# modem-breakout.net
KiCad netlist of a schematic drawn in EAGLE
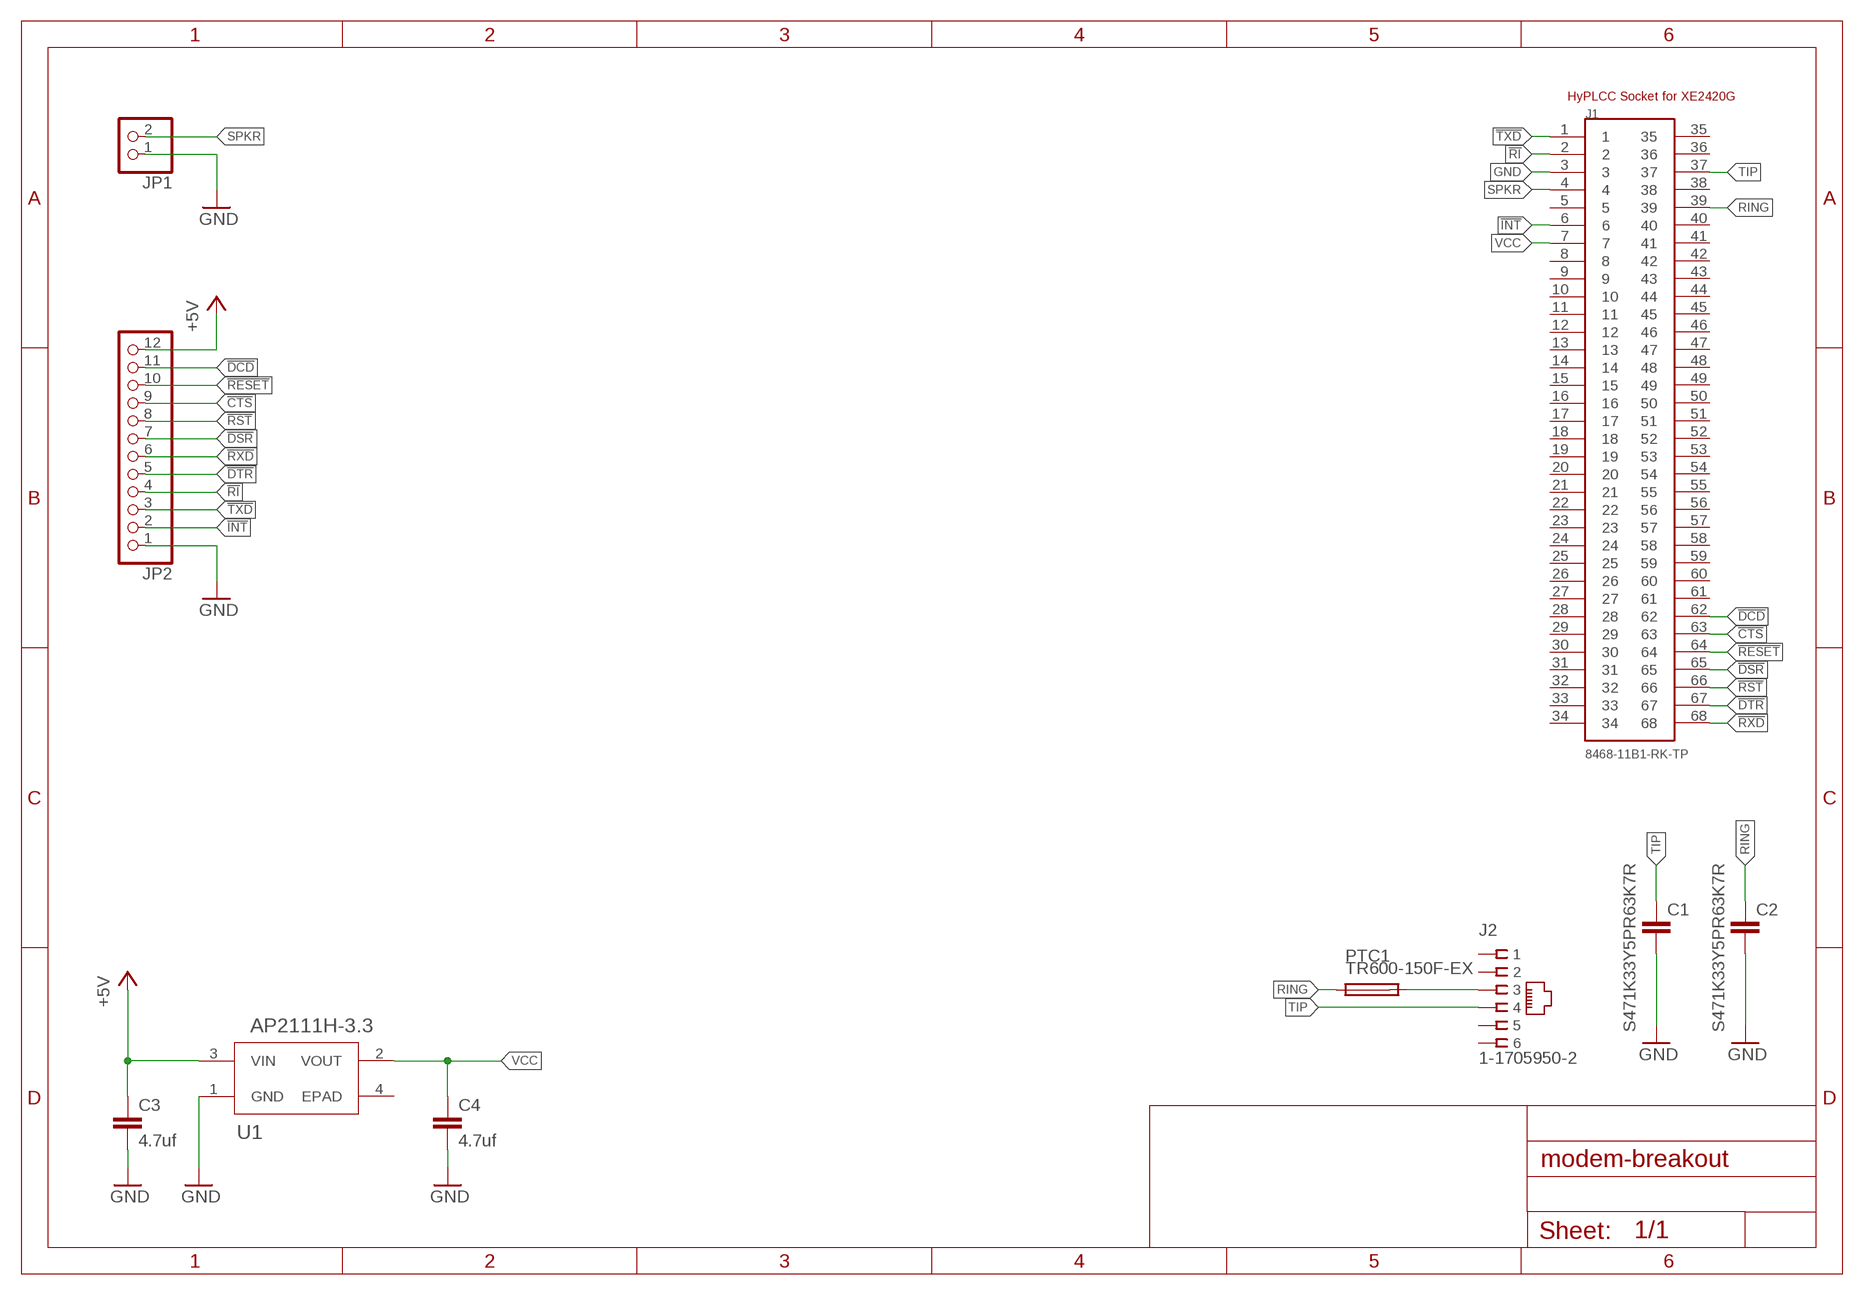
[diagram p0: schematic, sheet 1]

(export (version "E")
  (design (tool "Eeschema 10.0.6"))
  (components
    (comp (ref "C1")
      (value "S471K33Y5PR63K7R")
      (footprint "eagle-import:C075-052X106")
      (libsource (lib "eagle-import") (part "C-EU075-052X106"))
    )
    (comp (ref "C2")
      (value "S471K33Y5PR63K7R")
      (footprint "eagle-import:C075-052X106")
      (libsource (lib "eagle-import") (part "C-EU075-052X106"))
    )
    (comp (ref "C3")
      (value "4.7uf")
      (footprint "eagle-import:C0805")
      (libsource (lib "eagle-import") (part "C-EUC0805"))
    )
    (comp (ref "C4")
      (value "4.7uf")
      (footprint "eagle-import:C0805")
      (libsource (lib "eagle-import") (part "C-EUC0805"))
    )
    (comp (ref "J1")
      (value "8468-11B1-RK-TP")
      (footprint "eagle-import:3M_8468-11B1-RK-TP")
      (fields (field (name "MF") "3M"))
      (libsource (lib "eagle-import") (part "8468-11B1-RK-TP"))
    )
    (comp (ref "J2")
      (value "1-1705950-2")
      (footprint "eagle-import:RJ11-NO_SHIELD")
      (fields (field (name "MF") "TYCO ELECTRONICS") (field (name "MPN") "RJ11-2L-B"))
      (libsource (lib "eagle-import") (part "RJ11-2L-B"))
    )
    (comp (ref "JP1")
      (value "PINHD-1X2")
      (footprint "eagle-import:1X02")
      (libsource (lib "eagle-import") (part "PINHD-1X2"))
    )
    (comp (ref "JP2")
      (value "PINHD-1X12")
      (footprint "eagle-import:1X12")
      (libsource (lib "eagle-import") (part "PINHD-1X12"))
    )
    (comp (ref "PTC1")
      (value "TR600-150F-EX")
      (footprint "eagle-import:13.50X6.00")
      (libsource (lib "eagle-import") (part "TR600-150F-EX"))
    )
    (comp (ref "U1")
      (value "AP2111H-3.3")
      (footprint "eagle-import:SOT-223_DIO-M")
      (fields (field (name "MANUFACTURER_PART_NUMBER") "AP2111H-3.3TRG1"))
      (libsource (lib "eagle-import") (part "AP2111H-3.3TRG1SOT-223_DIO-M"))
    )
  )
  (nets
    (net (code "1") (name "+5V") (class "Default")
      (node (ref "C3") (pin "1") (pinfunction "1_1") (pintype "passive"))
      (node (ref "JP2") (pin "12") (pinfunction "12_12") (pintype "passive"))
      (node (ref "U1") (pin "3") (pinfunction "VIN_3") (pintype "input"))
    )
    (net (code "2") (name "/~{CTS}") (class "Default")
      (node (ref "J1") (pin "63") (pinfunction "63_63") (pintype "passive"))
      (node (ref "JP2") (pin "9") (pinfunction "9_9") (pintype "passive"))
    )
    (net (code "3") (name "/~{DCD}") (class "Default")
      (node (ref "J1") (pin "62") (pinfunction "62_62") (pintype "passive"))
      (node (ref "JP2") (pin "11") (pinfunction "11_11") (pintype "passive"))
    )
    (net (code "4") (name "/~{DSR}") (class "Default")
      (node (ref "J1") (pin "65") (pinfunction "65_65") (pintype "passive"))
      (node (ref "JP2") (pin "7") (pinfunction "7_7") (pintype "passive"))
    )
    (net (code "5") (name "/~{DTR}") (class "Default")
      (node (ref "J1") (pin "67") (pinfunction "67_67") (pintype "passive"))
      (node (ref "JP2") (pin "5") (pinfunction "5_5") (pintype "passive"))
    )
    (net (code "6") (name "/~{INT}") (class "Default")
      (node (ref "J1") (pin "6") (pinfunction "6_6") (pintype "passive"))
      (node (ref "JP2") (pin "2") (pinfunction "2_2") (pintype "passive"))
    )
    (net (code "7") (name "/~{RESET}") (class "Default")
      (node (ref "J1") (pin "64") (pinfunction "64_64") (pintype "passive"))
      (node (ref "JP2") (pin "10") (pinfunction "10_10") (pintype "passive"))
    )
    (net (code "8") (name "/~{RI}") (class "Default")
      (node (ref "J1") (pin "2") (pinfunction "2_2") (pintype "passive"))
      (node (ref "JP2") (pin "4") (pinfunction "4_4") (pintype "passive"))
    )
    (net (code "9") (name "/~{RST}") (class "Default")
      (node (ref "J1") (pin "66") (pinfunction "66_66") (pintype "passive"))
      (node (ref "JP2") (pin "8") (pinfunction "8_8") (pintype "passive"))
    )
    (net (code "10") (name "/~{RXD}") (class "Default")
      (node (ref "J1") (pin "68") (pinfunction "68_68") (pintype "passive"))
      (node (ref "JP2") (pin "6") (pinfunction "6_6") (pintype "passive"))
    )
    (net (code "11") (name "/~{TXD}") (class "Default")
      (node (ref "J1") (pin "1") (pinfunction "1_1") (pintype "passive"))
      (node (ref "JP2") (pin "3") (pinfunction "3_3") (pintype "passive"))
    )
    (net (code "12") (name "GND") (class "Default")
      (node (ref "C1") (pin "2") (pinfunction "2_2") (pintype "passive"))
      (node (ref "C2") (pin "2") (pinfunction "2_2") (pintype "passive"))
      (node (ref "C3") (pin "2") (pinfunction "2_2") (pintype "passive"))
      (node (ref "C4") (pin "2") (pinfunction "2_2") (pintype "passive"))
      (node (ref "J1") (pin "3") (pinfunction "3_3") (pintype "passive"))
      (node (ref "JP1") (pin "1") (pinfunction "1_1") (pintype "passive"))
      (node (ref "JP2") (pin "1") (pinfunction "1_1") (pintype "passive"))
      (node (ref "U1") (pin "1") (pinfunction "GND_1") (pintype "power_in"))
    )
    (net (code "13") (name "Net-(PTC1-2)") (class "Default")
      (node (ref "J2") (pin "3") (pinfunction "3_3") (pintype "passive"))
      (node (ref "PTC1") (pin "P$2") (pinfunction "2_P$2") (pintype "passive"))
    )
    (net (code "14") (name "RING") (class "Default")
      (node (ref "C2") (pin "1") (pinfunction "1_1") (pintype "passive"))
      (node (ref "J1") (pin "39") (pinfunction "39_39") (pintype "passive"))
      (node (ref "PTC1") (pin "P$1") (pinfunction "1_P$1") (pintype "passive"))
    )
    (net (code "15") (name "SPKR") (class "Default")
      (node (ref "J1") (pin "4") (pinfunction "4_4") (pintype "passive"))
      (node (ref "JP1") (pin "2") (pinfunction "2_2") (pintype "passive"))
    )
    (net (code "16") (name "TIP") (class "Default")
      (node (ref "C1") (pin "1") (pinfunction "1_1") (pintype "passive"))
      (node (ref "J1") (pin "37") (pinfunction "37_37") (pintype "passive"))
      (node (ref "J2") (pin "4") (pinfunction "4_4") (pintype "passive"))
    )
    (net (code "17") (name "VCC") (class "Default")
      (node (ref "C4") (pin "1") (pinfunction "1_1") (pintype "passive"))
      (node (ref "J1") (pin "7") (pinfunction "7_7") (pintype "passive"))
      (node (ref "U1") (pin "2") (pinfunction "VOUT_2") (pintype "output"))
    )
    (net (code "18") (name "unconnected-(J1-Pad5)") (class "Default")
      (node (ref "J1") (pin "5") (pinfunction "5_5") (pintype "passive"))
    )
    (net (code "19") (name "unconnected-(J1-Pad8)") (class "Default")
      (node (ref "J1") (pin "8") (pinfunction "8_8") (pintype "passive"))
    )
    (net (code "20") (name "unconnected-(J1-Pad9)") (class "Default")
      (node (ref "J1") (pin "9") (pinfunction "9_9") (pintype "passive"))
    )
    (net (code "21") (name "unconnected-(J1-Pad10)") (class "Default")
      (node (ref "J1") (pin "10") (pinfunction "10_10") (pintype "passive"))
    )
    (net (code "22") (name "unconnected-(J1-Pad11)") (class "Default")
      (node (ref "J1") (pin "11") (pinfunction "11_11") (pintype "passive"))
    )
    (net (code "23") (name "unconnected-(J1-Pad12)") (class "Default")
      (node (ref "J1") (pin "12") (pinfunction "12_12") (pintype "passive"))
    )
    (net (code "24") (name "unconnected-(J1-Pad13)") (class "Default")
      (node (ref "J1") (pin "13") (pinfunction "13_13") (pintype "passive"))
    )
    (net (code "25") (name "unconnected-(J1-Pad14)") (class "Default")
      (node (ref "J1") (pin "14") (pinfunction "14_14") (pintype "passive"))
    )
    (net (code "26") (name "unconnected-(J1-Pad15)") (class "Default")
      (node (ref "J1") (pin "15") (pinfunction "15_15") (pintype "passive"))
    )
    (net (code "27") (name "unconnected-(J1-Pad16)") (class "Default")
      (node (ref "J1") (pin "16") (pinfunction "16_16") (pintype "passive"))
    )
    (net (code "28") (name "unconnected-(J1-Pad17)") (class "Default")
      (node (ref "J1") (pin "17") (pinfunction "17_17") (pintype "passive"))
    )
    (net (code "29") (name "unconnected-(J1-Pad18)") (class "Default")
      (node (ref "J1") (pin "18") (pinfunction "18_18") (pintype "passive"))
    )
    (net (code "30") (name "unconnected-(J1-Pad19)") (class "Default")
      (node (ref "J1") (pin "19") (pinfunction "19_19") (pintype "passive"))
    )
    (net (code "31") (name "unconnected-(J1-Pad20)") (class "Default")
      (node (ref "J1") (pin "20") (pinfunction "20_20") (pintype "passive"))
    )
    (net (code "32") (name "unconnected-(J1-Pad21)") (class "Default")
      (node (ref "J1") (pin "21") (pinfunction "21_21") (pintype "passive"))
    )
    (net (code "33") (name "unconnected-(J1-Pad22)") (class "Default")
      (node (ref "J1") (pin "22") (pinfunction "22_22") (pintype "passive"))
    )
    (net (code "34") (name "unconnected-(J1-Pad23)") (class "Default")
      (node (ref "J1") (pin "23") (pinfunction "23_23") (pintype "passive"))
    )
    (net (code "35") (name "unconnected-(J1-Pad24)") (class "Default")
      (node (ref "J1") (pin "24") (pinfunction "24_24") (pintype "passive"))
    )
    (net (code "36") (name "unconnected-(J1-Pad25)") (class "Default")
      (node (ref "J1") (pin "25") (pinfunction "25_25") (pintype "passive"))
    )
    (net (code "37") (name "unconnected-(J1-Pad26)") (class "Default")
      (node (ref "J1") (pin "26") (pinfunction "26_26") (pintype "passive"))
    )
    (net (code "38") (name "unconnected-(J1-Pad27)") (class "Default")
      (node (ref "J1") (pin "27") (pinfunction "27_27") (pintype "passive"))
    )
    (net (code "39") (name "unconnected-(J1-Pad28)") (class "Default")
      (node (ref "J1") (pin "28") (pinfunction "28_28") (pintype "passive"))
    )
    (net (code "40") (name "unconnected-(J1-Pad29)") (class "Default")
      (node (ref "J1") (pin "29") (pinfunction "29_29") (pintype "passive"))
    )
    (net (code "41") (name "unconnected-(J1-Pad30)") (class "Default")
      (node (ref "J1") (pin "30") (pinfunction "30_30") (pintype "passive"))
    )
    (net (code "42") (name "unconnected-(J1-Pad31)") (class "Default")
      (node (ref "J1") (pin "31") (pinfunction "31_31") (pintype "passive"))
    )
    (net (code "43") (name "unconnected-(J1-Pad32)") (class "Default")
      (node (ref "J1") (pin "32") (pinfunction "32_32") (pintype "passive"))
    )
    (net (code "44") (name "unconnected-(J1-Pad33)") (class "Default")
      (node (ref "J1") (pin "33") (pinfunction "33_33") (pintype "passive"))
    )
    (net (code "45") (name "unconnected-(J1-Pad34)") (class "Default")
      (node (ref "J1") (pin "34") (pinfunction "34_34") (pintype "passive"))
    )
    (net (code "46") (name "unconnected-(J1-Pad35)") (class "Default")
      (node (ref "J1") (pin "35") (pinfunction "35_35") (pintype "passive"))
    )
    (net (code "47") (name "unconnected-(J1-Pad36)") (class "Default")
      (node (ref "J1") (pin "36") (pinfunction "36_36") (pintype "passive"))
    )
    (net (code "48") (name "unconnected-(J1-Pad38)") (class "Default")
      (node (ref "J1") (pin "38") (pinfunction "38_38") (pintype "passive"))
    )
    (net (code "49") (name "unconnected-(J1-Pad40)") (class "Default")
      (node (ref "J1") (pin "40") (pinfunction "40_40") (pintype "passive"))
    )
    (net (code "50") (name "unconnected-(J1-Pad41)") (class "Default")
      (node (ref "J1") (pin "41") (pinfunction "41_41") (pintype "passive"))
    )
    (net (code "51") (name "unconnected-(J1-Pad42)") (class "Default")
      (node (ref "J1") (pin "42") (pinfunction "42_42") (pintype "passive"))
    )
    (net (code "52") (name "unconnected-(J1-Pad43)") (class "Default")
      (node (ref "J1") (pin "43") (pinfunction "43_43") (pintype "passive"))
    )
    (net (code "53") (name "unconnected-(J1-Pad44)") (class "Default")
      (node (ref "J1") (pin "44") (pinfunction "44_44") (pintype "passive"))
    )
    (net (code "54") (name "unconnected-(J1-Pad45)") (class "Default")
      (node (ref "J1") (pin "45") (pinfunction "45_45") (pintype "passive"))
    )
    (net (code "55") (name "unconnected-(J1-Pad46)") (class "Default")
      (node (ref "J1") (pin "46") (pinfunction "46_46") (pintype "passive"))
    )
    (net (code "56") (name "unconnected-(J1-Pad47)") (class "Default")
      (node (ref "J1") (pin "47") (pinfunction "47_47") (pintype "passive"))
    )
    (net (code "57") (name "unconnected-(J1-Pad48)") (class "Default")
      (node (ref "J1") (pin "48") (pinfunction "48_48") (pintype "passive"))
    )
    (net (code "58") (name "unconnected-(J1-Pad49)") (class "Default")
      (node (ref "J1") (pin "49") (pinfunction "49_49") (pintype "passive"))
    )
    (net (code "59") (name "unconnected-(J1-Pad50)") (class "Default")
      (node (ref "J1") (pin "50") (pinfunction "50_50") (pintype "passive"))
    )
    (net (code "60") (name "unconnected-(J1-Pad51)") (class "Default")
      (node (ref "J1") (pin "51") (pinfunction "51_51") (pintype "passive"))
    )
    (net (code "61") (name "unconnected-(J1-Pad52)") (class "Default")
      (node (ref "J1") (pin "52") (pinfunction "52_52") (pintype "passive"))
    )
    (net (code "62") (name "unconnected-(J1-Pad53)") (class "Default")
      (node (ref "J1") (pin "53") (pinfunction "53_53") (pintype "passive"))
    )
    (net (code "63") (name "unconnected-(J1-Pad54)") (class "Default")
      (node (ref "J1") (pin "54") (pinfunction "54_54") (pintype "passive"))
    )
    (net (code "64") (name "unconnected-(J1-Pad55)") (class "Default")
      (node (ref "J1") (pin "55") (pinfunction "55_55") (pintype "passive"))
    )
    (net (code "65") (name "unconnected-(J1-Pad56)") (class "Default")
      (node (ref "J1") (pin "56") (pinfunction "56_56") (pintype "passive"))
    )
    (net (code "66") (name "unconnected-(J1-Pad57)") (class "Default")
      (node (ref "J1") (pin "57") (pinfunction "57_57") (pintype "passive"))
    )
    (net (code "67") (name "unconnected-(J1-Pad58)") (class "Default")
      (node (ref "J1") (pin "58") (pinfunction "58_58") (pintype "passive"))
    )
    (net (code "68") (name "unconnected-(J1-Pad59)") (class "Default")
      (node (ref "J1") (pin "59") (pinfunction "59_59") (pintype "passive"))
    )
    (net (code "69") (name "unconnected-(J1-Pad60)") (class "Default")
      (node (ref "J1") (pin "60") (pinfunction "60_60") (pintype "passive"))
    )
    (net (code "70") (name "unconnected-(J1-Pad61)") (class "Default")
      (node (ref "J1") (pin "61") (pinfunction "61_61") (pintype "passive"))
    )
    (net (code "71") (name "unconnected-(J2-Pad1)") (class "Default")
      (node (ref "J2") (pin "1") (pinfunction "1_1") (pintype "passive"))
    )
    (net (code "72") (name "unconnected-(J2-Pad2)") (class "Default")
      (node (ref "J2") (pin "2") (pinfunction "2_2") (pintype "passive"))
    )
    (net (code "73") (name "unconnected-(J2-Pad5)") (class "Default")
      (node (ref "J2") (pin "5") (pinfunction "5_5") (pintype "passive"))
    )
    (net (code "74") (name "unconnected-(J2-Pad6)") (class "Default")
      (node (ref "J2") (pin "6") (pinfunction "6_6") (pintype "passive"))
    )
    (net (code "75") (name "unconnected-(U1-EPAD-Pad4)") (class "Default")
      (node (ref "U1") (pin "4") (pinfunction "EPAD_4") (pintype "passive"))
    )
  )
)
